# Brew-Bubbles.net
KiCad netlist of a schematic drawn in EAGLE
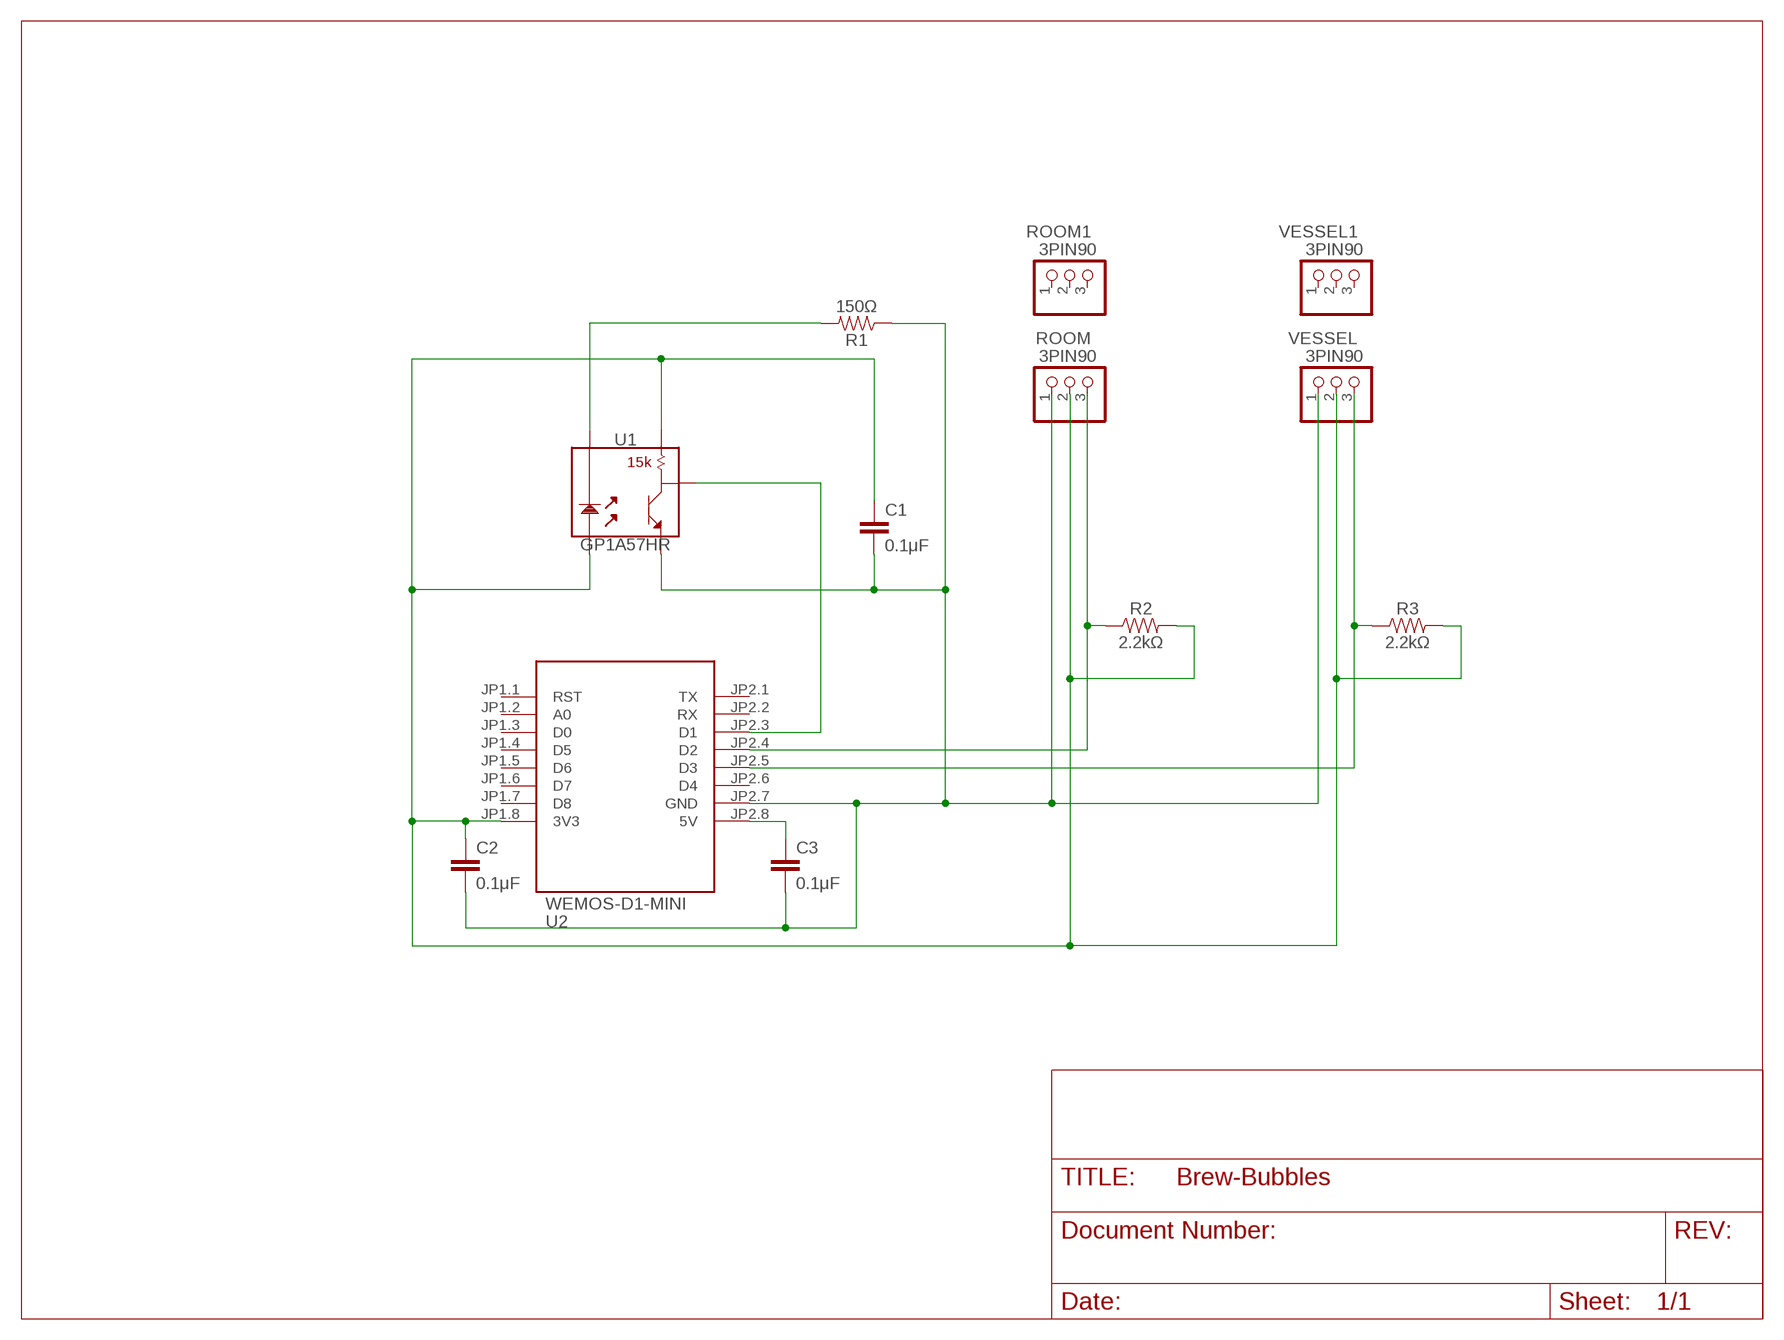
[diagram p0: schematic, sheet 1]

(export (version "E")
  (design (tool "Eeschema 10.0.6"))
  (components
    (comp (ref "C1")
      (value "0.1μF")
      (footprint "eagle-import:C025-024X044")
      (libsource (lib "eagle-import") (part "C-EU025-024X044"))
    )
    (comp (ref "C2")
      (value "0.1μF")
      (footprint "eagle-import:C025-024X044")
      (libsource (lib "eagle-import") (part "C-EU025-024X044"))
    )
    (comp (ref "C3")
      (value "0.1μF")
      (footprint "eagle-import:C025-024X044")
      (libsource (lib "eagle-import") (part "C-EU025-024X044"))
    )
    (comp (ref "R1")
      (value "150Ω")
      (footprint "eagle-import:AXIAL-0.3")
      (libsource (lib "eagle-import") (part "330OHM-HORIZ-1/10W-5%"))
    )
    (comp (ref "R2")
      (value "2.2kΩ")
      (footprint "eagle-import:AXIAL-0.3")
      (libsource (lib "eagle-import") (part "330OHM-HORIZ-1/10W-5%"))
    )
    (comp (ref "R3")
      (value "2.2kΩ")
      (footprint "eagle-import:AXIAL-0.3")
      (libsource (lib "eagle-import") (part "330OHM-HORIZ-1/10W-5%"))
    )
    (comp (ref "ROOM")
      (value "3PIN90")
      (footprint "eagle-import:1X03_90")
      (libsource (lib "eagle-import") (part "PINHD-1X3/90"))
    )
    (comp (ref "ROOM1")
      (value "3PIN90")
      (footprint "eagle-import:1X03_90")
      (libsource (lib "eagle-import") (part "PINHD-1X3/90"))
    )
    (comp (ref "U1")
      (value "GP1A57HR")
      (footprint "eagle-import:GP1A57HR")
      (libsource (lib "eagle-import") (part "GP1A57HR"))
    )
    (comp (ref "U2")
      (value "WEMOS-D1-MINI")
      (footprint "eagle-import:WEMOS-D1-MINI-SHIELD")
      (libsource (lib "eagle-import") (part "WEMOS-D1-MINI-SHIELD"))
    )
    (comp (ref "VESSEL")
      (value "3PIN90")
      (footprint "eagle-import:1X03_90")
      (libsource (lib "eagle-import") (part "PINHD-1X3/90"))
    )
    (comp (ref "VESSEL1")
      (value "3PIN90")
      (footprint "eagle-import:1X03_90")
      (libsource (lib "eagle-import") (part "PINHD-1X3/90"))
    )
  )
  (nets
    (net (code "1") (name "Net-(R1-1)") (class "Default")
      (node (ref "C1") (pin "2") (pinfunction "2_2") (pintype "passive"))
      (node (ref "C2") (pin "2") (pinfunction "2_2") (pintype "passive"))
      (node (ref "C3") (pin "2") (pinfunction "2_2") (pintype "passive"))
      (node (ref "R1") (pin "P$1") (pinfunction "1_P$1") (pintype "passive"))
      (node (ref "ROOM") (pin "1") (pinfunction "1_1") (pintype "passive"))
      (node (ref "U1") (pin "5") (pinfunction "5_5") (pintype "bidirectional"))
      (node (ref "U2") (pin "JP2.7") (pinfunction "GND_JP2.7") (pintype "power_in"))
      (node (ref "VESSEL") (pin "1") (pinfunction "1_1") (pintype "passive"))
    )
    (net (code "2") (name "Net-(R1-2)") (class "Default")
      (node (ref "R1") (pin "P$2") (pinfunction "2_P$2") (pintype "passive"))
      (node (ref "U1") (pin "2") (pinfunction "2_2") (pintype "bidirectional"))
    )
    (net (code "3") (name "Net-(R2-1)") (class "Default")
      (node (ref "R2") (pin "P$1") (pinfunction "1_P$1") (pintype "passive"))
      (node (ref "ROOM") (pin "3") (pinfunction "3_3") (pintype "passive"))
      (node (ref "U2") (pin "JP2.4") (pinfunction "D2_JP2.4") (pintype "bidirectional"))
    )
    (net (code "4") (name "Net-(R2-2)") (class "Default")
      (node (ref "C1") (pin "1") (pinfunction "1_1") (pintype "passive"))
      (node (ref "C2") (pin "1") (pinfunction "1_1") (pintype "passive"))
      (node (ref "R2") (pin "P$2") (pinfunction "2_P$2") (pintype "passive"))
      (node (ref "R3") (pin "P$2") (pinfunction "2_P$2") (pintype "passive"))
      (node (ref "ROOM") (pin "2") (pinfunction "2_2") (pintype "passive"))
      (node (ref "U1") (pin "1") (pinfunction "1_1") (pintype "bidirectional"))
      (node (ref "U1") (pin "3") (pinfunction "3_3") (pintype "bidirectional"))
      (node (ref "U2") (pin "JP1.8") (pinfunction "3V3_JP1.8") (pintype "power_in"))
      (node (ref "VESSEL") (pin "2") (pinfunction "2_2") (pintype "passive"))
    )
    (net (code "5") (name "Net-(R3-1)") (class "Default")
      (node (ref "R3") (pin "P$1") (pinfunction "1_P$1") (pintype "passive"))
      (node (ref "U2") (pin "JP2.5") (pinfunction "D3_JP2.5") (pintype "bidirectional"))
      (node (ref "VESSEL") (pin "3") (pinfunction "3_3") (pintype "passive"))
    )
    (net (code "6") (name "Net-(U2-5V)") (class "Default")
      (node (ref "C3") (pin "1") (pinfunction "1_1") (pintype "passive"))
      (node (ref "U2") (pin "JP2.8") (pinfunction "5V_JP2.8") (pintype "power_in"))
    )
    (net (code "7") (name "Net-(U2-D1)") (class "Default")
      (node (ref "U1") (pin "4") (pinfunction "4_4") (pintype "bidirectional"))
      (node (ref "U2") (pin "JP2.3") (pinfunction "D1_JP2.3") (pintype "bidirectional"))
    )
    (net (code "8") (name "unconnected-(ROOM1-Pad1)") (class "Default")
      (node (ref "ROOM1") (pin "1") (pinfunction "1_1") (pintype "passive"))
    )
    (net (code "9") (name "unconnected-(ROOM1-Pad2)") (class "Default")
      (node (ref "ROOM1") (pin "2") (pinfunction "2_2") (pintype "passive"))
    )
    (net (code "10") (name "unconnected-(ROOM1-Pad3)") (class "Default")
      (node (ref "ROOM1") (pin "3") (pinfunction "3_3") (pintype "passive"))
    )
    (net (code "11") (name "unconnected-(U2-A0-PadJP1.2)") (class "Default")
      (node (ref "U2") (pin "JP1.2") (pinfunction "A0_JP1.2") (pintype "bidirectional"))
    )
    (net (code "12") (name "unconnected-(U2-D0-PadJP1.3)") (class "Default")
      (node (ref "U2") (pin "JP1.3") (pinfunction "D0_JP1.3") (pintype "bidirectional"))
    )
    (net (code "13") (name "unconnected-(U2-D4-PadJP2.6)") (class "Default")
      (node (ref "U2") (pin "JP2.6") (pinfunction "D4_JP2.6") (pintype "bidirectional"))
    )
    (net (code "14") (name "unconnected-(U2-D5-PadJP1.4)") (class "Default")
      (node (ref "U2") (pin "JP1.4") (pinfunction "D5_JP1.4") (pintype "bidirectional"))
    )
    (net (code "15") (name "unconnected-(U2-D6-PadJP1.5)") (class "Default")
      (node (ref "U2") (pin "JP1.5") (pinfunction "D6_JP1.5") (pintype "bidirectional"))
    )
    (net (code "16") (name "unconnected-(U2-D7-PadJP1.6)") (class "Default")
      (node (ref "U2") (pin "JP1.6") (pinfunction "D7_JP1.6") (pintype "bidirectional"))
    )
    (net (code "17") (name "unconnected-(U2-D8-PadJP1.7)") (class "Default")
      (node (ref "U2") (pin "JP1.7") (pinfunction "D8_JP1.7") (pintype "bidirectional"))
    )
    (net (code "18") (name "unconnected-(U2-RST-PadJP1.1)") (class "Default")
      (node (ref "U2") (pin "JP1.1") (pinfunction "RST_JP1.1") (pintype "bidirectional"))
    )
    (net (code "19") (name "unconnected-(U2-RX-PadJP2.2)") (class "Default")
      (node (ref "U2") (pin "JP2.2") (pinfunction "RX_JP2.2") (pintype "bidirectional"))
    )
    (net (code "20") (name "unconnected-(U2-TX-PadJP2.1)") (class "Default")
      (node (ref "U2") (pin "JP2.1") (pinfunction "TX_JP2.1") (pintype "bidirectional"))
    )
    (net (code "21") (name "unconnected-(VESSEL1-Pad1)") (class "Default")
      (node (ref "VESSEL1") (pin "1") (pinfunction "1_1") (pintype "passive"))
    )
    (net (code "22") (name "unconnected-(VESSEL1-Pad2)") (class "Default")
      (node (ref "VESSEL1") (pin "2") (pinfunction "2_2") (pintype "passive"))
    )
    (net (code "23") (name "unconnected-(VESSEL1-Pad3)") (class "Default")
      (node (ref "VESSEL1") (pin "3") (pinfunction "3_3") (pintype "passive"))
    )
  )
)
